# CanLogger_V22.net
KiCad netlist of a schematic drawn in EAGLE
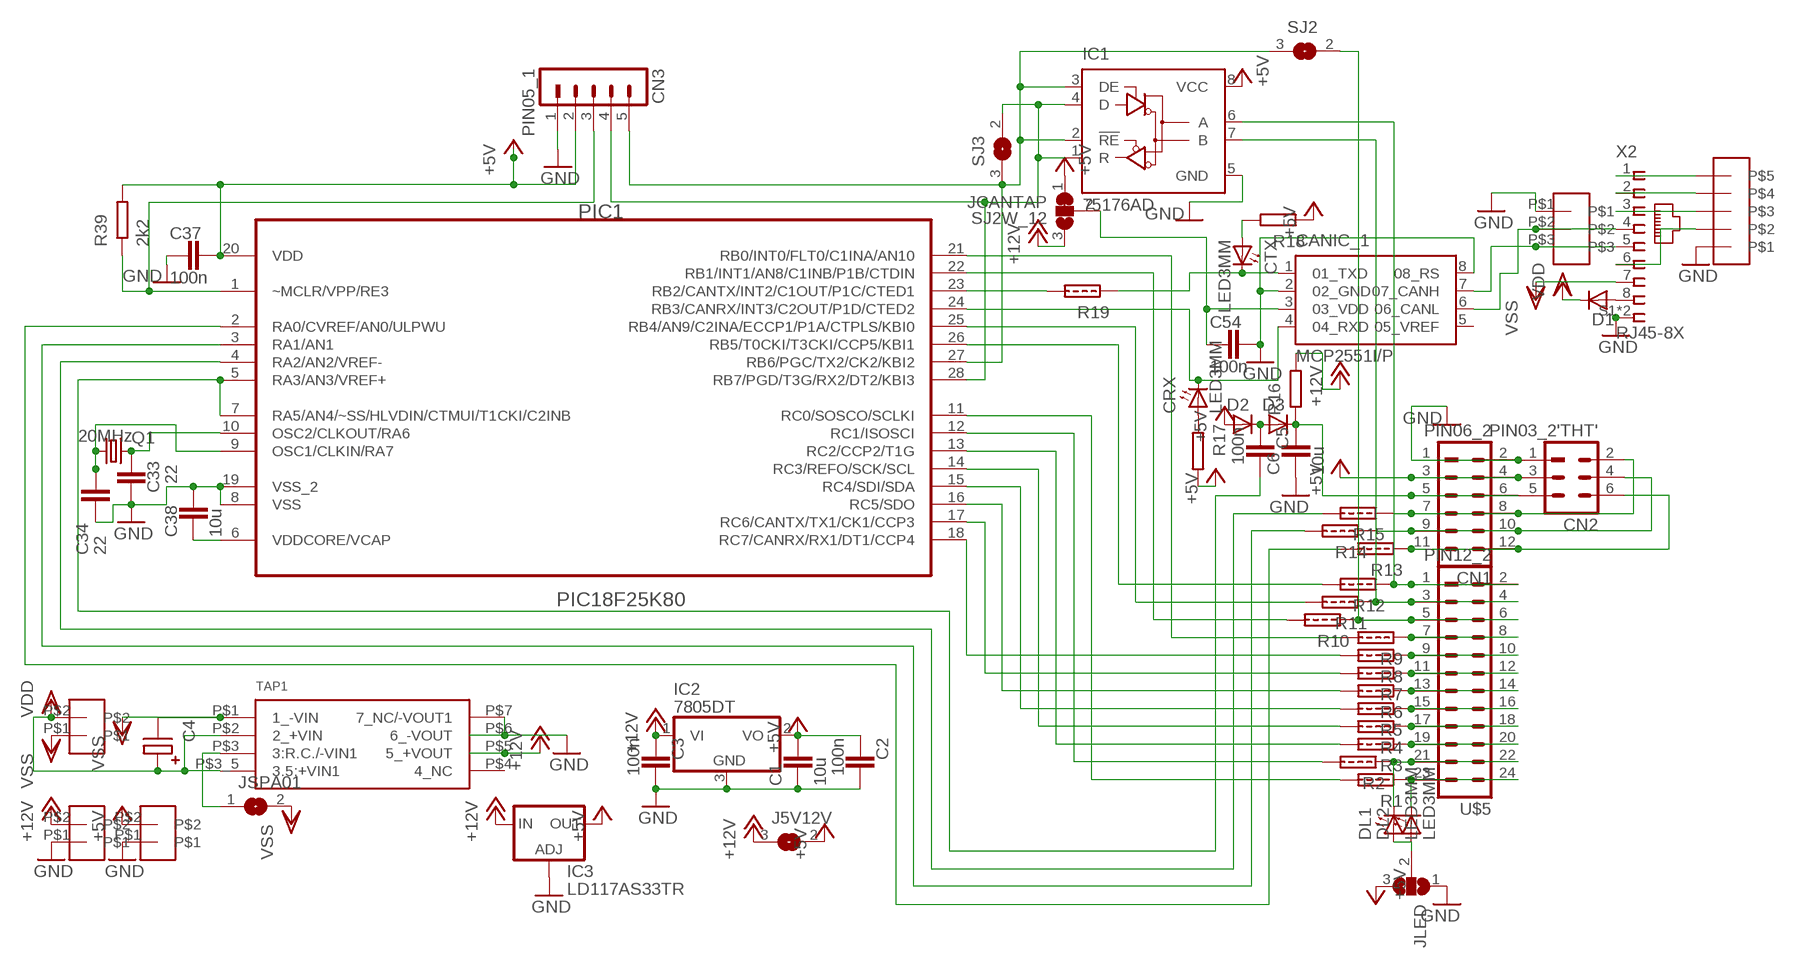
[diagram p0: schematic, sheet 1]

(export (version "E")
  (design (tool "Eeschema 10.0.6"))
  (components
    (comp (ref "C1")
      (value "10u")
      (footprint "eagle-import:R0805")
      (libsource (lib "eagle-import") (part "C0805"))
    )
    (comp (ref "C2")
      (value "100n")
      (footprint "eagle-import:R0805")
      (libsource (lib "eagle-import") (part "C0805"))
    )
    (comp (ref "C3")
      (value "100n")
      (footprint "eagle-import:R0805")
      (libsource (lib "eagle-import") (part "C0805"))
    )
    (comp (ref "C4")
      (value "C_EL1R05")
      (footprint "eagle-import:C_EL1RASZT05")
      (libsource (lib "eagle-import") (part "C_EL1R05"))
    )
    (comp (ref "C5")
      (value "100n")
      (footprint "eagle-import:R0805")
      (libsource (lib "eagle-import") (part "C0805"))
    )
    (comp (ref "C6")
      (value "10u")
      (footprint "eagle-import:R0805")
      (libsource (lib "eagle-import") (part "C0805"))
    )
    (comp (ref "C33")
      (value "22")
      (footprint "eagle-import:R0805")
      (libsource (lib "eagle-import") (part "C0805"))
    )
    (comp (ref "C34")
      (value "22")
      (footprint "eagle-import:R0805")
      (libsource (lib "eagle-import") (part "C0805"))
    )
    (comp (ref "C37")
      (value "100n")
      (footprint "eagle-import:R0805")
      (libsource (lib "eagle-import") (part "C0805"))
    )
    (comp (ref "C38")
      (value "10u")
      (footprint "eagle-import:R0805")
      (libsource (lib "eagle-import") (part "C0805"))
    )
    (comp (ref "C54")
      (value "100n")
      (footprint "eagle-import:R0805")
      (libsource (lib "eagle-import") (part "C0805"))
    )
    (comp (ref "CANIC_1")
      (value "MCP2551I/P")
      (footprint "eagle-import:DIL_8")
      (libsource (lib "eagle-import") (part "MCP2551I/P"))
    )
    (comp (ref "CN1")
      (value "PIN06_2")
      (footprint "eagle-import:PIN06_2")
      (libsource (lib "eagle-import") (part "PIN06_2"))
    )
    (comp (ref "CN2")
      (value "PIN03_2'THT'")
      (footprint "eagle-import:PIN03_2")
      (libsource (lib "eagle-import") (part "PIN03_2'THT'"))
    )
    (comp (ref "CN3")
      (value "PIN05_1")
      (footprint "eagle-import:PIN05_1")
      (libsource (lib "eagle-import") (part "PIN05_1"))
    )
    (comp (ref "CN_CAN")
      (value "FEHER_TUS_3")
      (footprint "eagle-import:FEHER_TUS_3")
      (libsource (lib "eagle-import") (part "FEHER_TUS_3"))
    )
    (comp (ref "CRX")
      (value "LED3MM")
      (footprint "eagle-import:LED3MM")
      (libsource (lib "eagle-import") (part "LED3MM"))
    )
    (comp (ref "CTX")
      (value "LED3MM")
      (footprint "eagle-import:LED3MM")
      (libsource (lib "eagle-import") (part "LED3MM"))
    )
    (comp (ref "D1")
      (value "D1RNAGY")
      (footprint "eagle-import:D1RASZTNAGY")
      (libsource (lib "eagle-import") (part "D1RNAGY"))
    )
    (comp (ref "D2")
      (value "D0805")
      (footprint "eagle-import:D0805")
      (libsource (lib "eagle-import") (part "D0805"))
    )
    (comp (ref "D3")
      (value "D0805")
      (footprint "eagle-import:D0805")
      (libsource (lib "eagle-import") (part "D0805"))
    )
    (comp (ref "DL1")
      (value "LED3MM")
      (footprint "eagle-import:LED3MM")
      (libsource (lib "eagle-import") (part "LED3MM"))
    )
    (comp (ref "DL2")
      (value "LED3MM")
      (footprint "eagle-import:LED3MM")
      (libsource (lib "eagle-import") (part "LED3MM"))
    )
    (comp (ref "IC1")
      (value "75176AD")
      (footprint "eagle-import:D_R-PDSO-G8")
      (libsource (lib "eagle-import") (part "75176AD"))
    )
    (comp (ref "IC2")
      (value "7805DT")
      (footprint "eagle-import:TO252")
      (libsource (lib "eagle-import") (part "78DT05"))
    )
    (comp (ref "IC3")
      (value "LD117AS33TR")
      (footprint "eagle-import:SOT223")
      (libsource (lib "eagle-import") (part "LD117A?S33TR"))
    )
    (comp (ref "J5V12V")
      (value "SJ")
      (footprint "eagle-import:SJ")
      (libsource (lib "eagle-import") (part "jumper2_SJ"))
    )
    (comp (ref "JCANTAP")
      (value "SJ2W_12")
      (footprint "eagle-import:SJ2_12")
      (libsource (lib "eagle-import") (part "SJ2W_12"))
    )
    (comp (ref "JLED")
      (value "SJ2W")
      (footprint "eagle-import:SJ2")
      (libsource (lib "eagle-import") (part "SJ2W"))
    )
    (comp (ref "JSPA01")
      (value "SJW")
      (footprint "eagle-import:SJW")
      (libsource (lib "eagle-import") (part "SJW"))
    )
    (comp (ref "PIC1")
      (value "PIC18F25K80")
      (footprint "eagle-import:SOIC127P1030X265-28N")
      (libsource (lib "eagle-import") (part "PIC18F25K80"))
    )
    (comp (ref "Q1")
      (value "20MHz")
      (footprint "eagle-import:XTAL_QS")
      (libsource (lib "eagle-import") (part "XTAL_2QS"))
    )
    (comp (ref "R1")
      (value "RNULL_EU0805")
      (footprint "eagle-import:R0805_C")
      (libsource (lib "eagle-import") (part "RNULL_EU0805"))
    )
    (comp (ref "R2")
      (value "RNULL_EU0805")
      (footprint "eagle-import:R0805_C")
      (libsource (lib "eagle-import") (part "RNULL_EU0805"))
    )
    (comp (ref "R3")
      (value "RNULL_EU0805")
      (footprint "eagle-import:R0805_C")
      (libsource (lib "eagle-import") (part "RNULL_EU0805"))
    )
    (comp (ref "R4")
      (value "RNULL_EU0805")
      (footprint "eagle-import:R0805_C")
      (libsource (lib "eagle-import") (part "RNULL_EU0805"))
    )
    (comp (ref "R5")
      (value "RNULL_EU0805")
      (footprint "eagle-import:R0805_C")
      (libsource (lib "eagle-import") (part "RNULL_EU0805"))
    )
    (comp (ref "R6")
      (value "RNULL_EU0805")
      (footprint "eagle-import:R0805_C")
      (libsource (lib "eagle-import") (part "RNULL_EU0805"))
    )
    (comp (ref "R7")
      (value "RNULL_EU0805")
      (footprint "eagle-import:R0805_C")
      (libsource (lib "eagle-import") (part "RNULL_EU0805"))
    )
    (comp (ref "R8")
      (value "RNULL_EU0805")
      (footprint "eagle-import:R0805_C")
      (libsource (lib "eagle-import") (part "RNULL_EU0805"))
    )
    (comp (ref "R9")
      (value "RNULL_EU0805")
      (footprint "eagle-import:R0805_C")
      (libsource (lib "eagle-import") (part "RNULL_EU0805"))
    )
    (comp (ref "R10")
      (value "RNULL_EU0805")
      (footprint "eagle-import:R0805_C")
      (libsource (lib "eagle-import") (part "RNULL_EU0805"))
    )
    (comp (ref "R11")
      (value "RNULL_EU0805")
      (footprint "eagle-import:R0805_C")
      (libsource (lib "eagle-import") (part "RNULL_EU0805"))
    )
    (comp (ref "R12")
      (value "RNULL_EU0805")
      (footprint "eagle-import:R0805_C")
      (libsource (lib "eagle-import") (part "RNULL_EU0805"))
    )
    (comp (ref "R13")
      (value "RNULL_EU0805")
      (footprint "eagle-import:R0805_C")
      (libsource (lib "eagle-import") (part "RNULL_EU0805"))
    )
    (comp (ref "R14")
      (value "RNULL_EU0805")
      (footprint "eagle-import:R0805_C")
      (libsource (lib "eagle-import") (part "RNULL_EU0805"))
    )
    (comp (ref "R15")
      (value "RNULL_EU0805")
      (footprint "eagle-import:R0805_C")
      (libsource (lib "eagle-import") (part "RNULL_EU0805"))
    )
    (comp (ref "R16")
      (value "R_EU0805")
      (footprint "eagle-import:R0805")
      (libsource (lib "eagle-import") (part "R_EU0805"))
    )
    (comp (ref "R17")
      (value "R_EU0805")
      (footprint "eagle-import:R0805")
      (libsource (lib "eagle-import") (part "R_EU0805"))
    )
    (comp (ref "R18")
      (value "R_EU0805")
      (footprint "eagle-import:R0805")
      (libsource (lib "eagle-import") (part "R_EU0805"))
    )
    (comp (ref "R19")
      (value "RNULL_EU0805")
      (footprint "eagle-import:R0805_C")
      (libsource (lib "eagle-import") (part "RNULL_EU0805"))
    )
    (comp (ref "R39")
      (value "2k2")
      (footprint "eagle-import:R0805")
      (libsource (lib "eagle-import") (part "R_EU0805"))
    )
    (comp (ref "SJ2")
      (value "SJ")
      (footprint "eagle-import:SJ")
      (libsource (lib "eagle-import") (part "jumper2_SJ"))
    )
    (comp (ref "SJ3")
      (value "SJ")
      (footprint "eagle-import:SJ")
      (libsource (lib "eagle-import") (part "jumper2_SJ"))
    )
    (comp (ref "TAP1")
      (value "SPA01_02C")
      (footprint "eagle-import:SPA01_02C")
      (libsource (lib "eagle-import") (part "SPA01_02C"))
    )
    (comp (ref "U$1")
      (value "FEHER_TUS_5")
      (footprint "eagle-import:FEHER_TUS_5")
      (libsource (lib "eagle-import") (part "FEHER_TUS_5"))
    )
    (comp (ref "U$2")
      (value "FEHER_TUS_2ALLO")
      (footprint "eagle-import:FEHER_TUS_2")
      (libsource (lib "eagle-import") (part "FEHER_TUS_2ALLO"))
    )
    (comp (ref "U$3")
      (value "FEHER_TUS_2ALLO")
      (footprint "eagle-import:FEHER_TUS_2")
      (libsource (lib "eagle-import") (part "FEHER_TUS_2ALLO"))
    )
    (comp (ref "U$4")
      (value "FEHER_TUS_2ALLO")
      (footprint "eagle-import:FEHER_TUS_2")
      (libsource (lib "eagle-import") (part "FEHER_TUS_2ALLO"))
    )
    (comp (ref "U$5")
      (value "PIN12_2")
      (footprint "eagle-import:PIN12_2")
      (libsource (lib "eagle-import") (part "PIN12_2"))
    )
    (comp (ref "X2")
      (value "RJ45-8X")
      (footprint "eagle-import:RJ45")
      (libsource (lib "eagle-import") (part "RJ45-8X"))
    )
  )
  (nets
    (net (code "1") (name "+5V") (class "Default")
      (node (ref "C1") (pin "1") (pinfunction "1_1") (pintype "passive"))
      (node (ref "C2") (pin "2") (pinfunction "2_2") (pintype "passive"))
      (node (ref "C37") (pin "1") (pinfunction "1_1") (pintype "passive"))
      (node (ref "CN1") (pin "3") (pinfunction "3_3") (pintype "passive"))
      (node (ref "CN1") (pin "4") (pinfunction "4_4") (pintype "passive"))
      (node (ref "CN2") (pin "3") (pinfunction "3_3") (pintype "passive"))
      (node (ref "CN3") (pin "2") (pinfunction "2_2") (pintype "passive"))
      (node (ref "D2") (pin "1") (pinfunction "A_1") (pintype "passive"))
      (node (ref "IC1") (pin "8") (pinfunction "VCC_8") (pintype "power_in"))
      (node (ref "IC2") (pin "2") (pinfunction "VO_2") (pintype "passive"))
      (node (ref "IC3") (pin "2") (pinfunction "OUT_2") (pintype "passive"))
      (node (ref "IC3") (pin "4") (pinfunction "OUT_4") (pintype "passive"))
      (node (ref "J5V12V") (pin "2") (pinfunction "2_2") (pintype "passive"))
      (node (ref "JCANTAP") (pin "1") (pinfunction "1_1") (pintype "passive"))
      (node (ref "JLED") (pin "3") (pinfunction "3_3") (pintype "passive"))
      (node (ref "PIC1") (pin "20") (pinfunction "VDD_20") (pintype "power_in"))
      (node (ref "R17") (pin "2") (pinfunction "E_2") (pintype "passive"))
      (node (ref "R18") (pin "1") (pinfunction "A_1") (pintype "passive"))
      (node (ref "R39") (pin "2") (pinfunction "E_2") (pintype "passive"))
      (node (ref "U$4") (pin "P$2") (pinfunction "P$2_P$2") (pintype "bidirectional"))
    )
    (net (code "2") (name "+12V") (class "Default")
      (node (ref "C3") (pin "2") (pinfunction "2_2") (pintype "passive"))
      (node (ref "IC2") (pin "1") (pinfunction "VI_1") (pintype "input"))
      (node (ref "IC3") (pin "3") (pinfunction "IN_3") (pintype "input"))
      (node (ref "J5V12V") (pin "3") (pinfunction "1_3") (pintype "passive"))
      (node (ref "JCANTAP") (pin "3") (pinfunction "3_3") (pintype "passive"))
      (node (ref "R16") (pin "2") (pinfunction "E_2") (pintype "passive"))
      (node (ref "TAP1") (pin "P$5") (pinfunction "5_+VOUT_P$5") (pintype "bidirectional"))
      (node (ref "U$3") (pin "P$2") (pinfunction "P$2_P$2") (pintype "bidirectional"))
    )
    (net (code "3") (name "GND") (class "Default")
      (node (ref "C1") (pin "2") (pinfunction "2_2") (pintype "passive"))
      (node (ref "C2") (pin "1") (pinfunction "1_1") (pintype "passive"))
      (node (ref "C3") (pin "1") (pinfunction "1_1") (pintype "passive"))
      (node (ref "C33") (pin "2") (pinfunction "2_2") (pintype "passive"))
      (node (ref "C34") (pin "2") (pinfunction "2_2") (pintype "passive"))
      (node (ref "C37") (pin "2") (pinfunction "2_2") (pintype "passive"))
      (node (ref "C38") (pin "1") (pinfunction "1_1") (pintype "passive"))
      (node (ref "C54") (pin "1") (pinfunction "1_1") (pintype "passive"))
      (node (ref "C6") (pin "2") (pinfunction "2_2") (pintype "passive"))
      (node (ref "CANIC_1") (pin "2") (pinfunction "02_GND_2") (pintype "power_in"))
      (node (ref "CANIC_1") (pin "8") (pinfunction "08_RS_8") (pintype "input"))
      (node (ref "CN1") (pin "1") (pinfunction "1_1") (pintype "passive"))
      (node (ref "CN1") (pin "2") (pinfunction "2_2") (pintype "passive"))
      (node (ref "CN2") (pin "1") (pinfunction "1_1") (pintype "passive"))
      (node (ref "CN3") (pin "1") (pinfunction "1_1") (pintype "passive"))
      (node (ref "CN_CAN") (pin "P$1") (pinfunction "P$1_P$1") (pintype "bidirectional"))
      (node (ref "IC1") (pin "5") (pinfunction "GND_5") (pintype "power_in"))
      (node (ref "IC2") (pin "3") (pinfunction "GND_3") (pintype "passive"))
      (node (ref "IC3") (pin "1") (pinfunction "ADJ_1") (pintype "input"))
      (node (ref "JLED") (pin "1") (pinfunction "1_1") (pintype "passive"))
      (node (ref "PIC1") (pin "19") (pinfunction "VSS_2_19") (pintype "power_in"))
      (node (ref "PIC1") (pin "8") (pinfunction "VSS_8") (pintype "power_in"))
      (node (ref "TAP1") (pin "P$6") (pinfunction "6_-VOUT_P$6") (pintype "bidirectional"))
      (node (ref "TAP1") (pin "P$7") (pinfunction "7_NC/-VOUT1_P$7") (pintype "bidirectional"))
      (node (ref "U$1") (pin "P$1") (pinfunction "P$1_P$1") (pintype "bidirectional"))
      (node (ref "U$3") (pin "P$1") (pinfunction "P$1_P$1") (pintype "bidirectional"))
      (node (ref "U$4") (pin "P$1") (pinfunction "P$1_P$1") (pintype "bidirectional"))
      (node (ref "X2") (pin "S1") (pinfunction "S_S1") (pintype "passive"))
      (node (ref "X2") (pin "S2") (pinfunction "S_S2") (pintype "passive"))
    )
    (net (code "4") (name "Net-(CANIC_1-01_TXD)") (class "Default")
      (node (ref "CANIC_1") (pin "1") (pinfunction "01_TXD_1") (pintype "input"))
      (node (ref "CTX") (pin "K") (pinfunction "C_K") (pintype "passive"))
      (node (ref "R19") (pin "1") (pinfunction "A_1") (pintype "passive"))
    )
    (net (code "5") (name "Net-(CANIC_1-03_VDD)") (class "Default")
      (node (ref "C54") (pin "2") (pinfunction "2_2") (pintype "passive"))
      (node (ref "CANIC_1") (pin "3") (pinfunction "03_VDD_3") (pintype "power_in"))
      (node (ref "JCANTAP") (pin "2") (pinfunction "2_2") (pintype "passive"))
    )
    (net (code "6") (name "Net-(CANIC_1-04_RXD)") (class "Default")
      (node (ref "CANIC_1") (pin "4") (pinfunction "04_RXD_4") (pintype "output"))
      (node (ref "CRX") (pin "K") (pinfunction "C_K") (pintype "passive"))
      (node (ref "PIC1") (pin "24") (pinfunction "RB3/CANRX/INT3/C2OUT/P1D/CTED2_24") (pintype "bidirectional"))
    )
    (net (code "7") (name "Net-(CANIC_1-06_CANL)") (class "Default")
      (node (ref "CANIC_1") (pin "6") (pinfunction "06_CANL_6") (pintype "bidirectional"))
      (node (ref "CN_CAN") (pin "P$2") (pinfunction "P$2_P$2") (pintype "bidirectional"))
      (node (ref "X2") (pin "4") (pinfunction "4_4") (pintype "passive"))
    )
    (net (code "8") (name "Net-(CANIC_1-07_CANH)") (class "Default")
      (node (ref "CANIC_1") (pin "7") (pinfunction "07_CANH_7") (pintype "bidirectional"))
      (node (ref "CN_CAN") (pin "P$3") (pinfunction "P$3_P$3") (pintype "bidirectional"))
      (node (ref "X2") (pin "5") (pinfunction "5_5") (pintype "passive"))
    )
    (net (code "9") (name "Net-(D1-A)") (class "Default")
      (node (ref "D1") (pin "P$1") (pinfunction "A_P$1") (pintype "passive"))
      (node (ref "X2") (pin "8") (pinfunction "8_8") (pintype "passive"))
    )
    (net (code "10") (name "Net-(D2-C)") (class "Default")
      (node (ref "C5") (pin "2") (pinfunction "2_2") (pintype "passive"))
      (node (ref "D2") (pin "2") (pinfunction "C_2") (pintype "passive"))
      (node (ref "D3") (pin "1") (pinfunction "A_1") (pintype "passive"))
    )
    (net (code "11") (name "Net-(D3-C)") (class "Default")
      (node (ref "C6") (pin "1") (pinfunction "1_1") (pintype "passive"))
      (node (ref "CN1") (pin "5") (pinfunction "5_5") (pintype "passive"))
      (node (ref "CN1") (pin "6") (pinfunction "6_6") (pintype "passive"))
      (node (ref "CN2") (pin "5") (pinfunction "5_5") (pintype "passive"))
      (node (ref "D3") (pin "2") (pinfunction "C_2") (pintype "passive"))
      (node (ref "R16") (pin "1") (pinfunction "A_1") (pintype "passive"))
    )
    (net (code "12") (name "Net-(DL1-C)") (class "Default")
      (node (ref "DL1") (pin "K") (pinfunction "C_K") (pintype "passive"))
      (node (ref "R2") (pin "1") (pinfunction "A_1") (pintype "passive"))
      (node (ref "U$5") (pin "21") (pinfunction "21_21") (pintype "passive"))
      (node (ref "U$5") (pin "22") (pinfunction "22_22") (pintype "passive"))
    )
    (net (code "13") (name "Net-(DL1-PadA)") (class "Default")
      (node (ref "DL1") (pin "A") (pinfunction "A_A") (pintype "passive"))
      (node (ref "DL2") (pin "A") (pinfunction "A_A") (pintype "passive"))
      (node (ref "JLED") (pin "2") (pinfunction "2_2") (pintype "passive"))
    )
    (net (code "14") (name "Net-(DL2-C)") (class "Default")
      (node (ref "DL2") (pin "K") (pinfunction "C_K") (pintype "passive"))
      (node (ref "R1") (pin "1") (pinfunction "A_1") (pintype "passive"))
      (node (ref "U$5") (pin "23") (pinfunction "23_23") (pintype "passive"))
      (node (ref "U$5") (pin "24") (pinfunction "24_24") (pintype "passive"))
    )
    (net (code "15") (name "Net-(IC1-A)") (class "Default")
      (node (ref "IC1") (pin "6") (pinfunction "A_6") (pintype "output"))
      (node (ref "R12") (pin "1") (pinfunction "A_1") (pintype "passive"))
      (node (ref "U$5") (pin "1") (pinfunction "1_1") (pintype "passive"))
      (node (ref "U$5") (pin "2") (pinfunction "2_2") (pintype "passive"))
    )
    (net (code "16") (name "Net-(IC1-B)") (class "Default")
      (node (ref "IC1") (pin "7") (pinfunction "B_7") (pintype "output"))
      (node (ref "R11") (pin "1") (pinfunction "A_1") (pintype "passive"))
      (node (ref "U$5") (pin "3") (pinfunction "3_3") (pintype "passive"))
      (node (ref "U$5") (pin "4") (pinfunction "4_4") (pintype "passive"))
    )
    (net (code "17") (name "Net-(IC1-D)") (class "Default")
      (node (ref "CN3") (pin "4") (pinfunction "4_4") (pintype "passive"))
      (node (ref "IC1") (pin "1") (pinfunction "R_1") (pintype "input"))
      (node (ref "IC1") (pin "4") (pinfunction "D_4") (pintype "input"))
      (node (ref "PIC1") (pin "28") (pinfunction "RB7/PGD/T3G/RX2/DT2/KBI3_28") (pintype "bidirectional"))
      (node (ref "SJ3") (pin "2") (pinfunction "2_2") (pintype "passive"))
    )
    (net (code "18") (name "Net-(IC1-DE)") (class "Default")
      (node (ref "CN3") (pin "5") (pinfunction "5_5") (pintype "passive"))
      (node (ref "IC1") (pin "2") (pinfunction "~{RE}_2") (pintype "input"))
      (node (ref "IC1") (pin "3") (pinfunction "DE_3") (pintype "input"))
      (node (ref "PIC1") (pin "27") (pinfunction "RB6/PGC/TX2/CK2/KBI2_27") (pintype "bidirectional"))
      (node (ref "SJ2") (pin "3") (pinfunction "1_3") (pintype "passive"))
      (node (ref "SJ3") (pin "3") (pinfunction "1_3") (pintype "passive"))
    )
    (net (code "19") (name "Net-(PIC1-OSC1{slash}CLKIN{slash}RA7)") (class "Default")
      (node (ref "C34") (pin "1") (pinfunction "1_1") (pintype "passive"))
      (node (ref "PIC1") (pin "9") (pinfunction "OSC1/CLKIN/RA7_9") (pintype "bidirectional"))
      (node (ref "Q1") (pin "1") (pinfunction "1_1") (pintype "passive"))
    )
    (net (code "20") (name "Net-(PIC1-OSC2{slash}CLKOUT{slash}RA6)") (class "Default")
      (node (ref "C33") (pin "1") (pinfunction "1_1") (pintype "passive"))
      (node (ref "PIC1") (pin "10") (pinfunction "OSC2/CLKOUT/RA6_10") (pintype "bidirectional"))
      (node (ref "Q1") (pin "2") (pinfunction "2_2") (pintype "passive"))
    )
    (net (code "21") (name "Net-(PIC1-RA0{slash}CVREF{slash}AN0{slash}ULPWU)") (class "Default")
      (node (ref "PIC1") (pin "2") (pinfunction "RA0/CVREF/AN0/ULPWU_2") (pintype "bidirectional"))
      (node (ref "R13") (pin "2") (pinfunction "E_2") (pintype "passive"))
    )
    (net (code "22") (name "Net-(PIC1-RA1{slash}AN1)") (class "Default")
      (node (ref "PIC1") (pin "3") (pinfunction "RA1/AN1_3") (pintype "bidirectional"))
      (node (ref "R14") (pin "2") (pinfunction "E_2") (pintype "passive"))
    )
    (net (code "23") (name "Net-(PIC1-RA2{slash}AN2{slash}VREF-)") (class "Default")
      (node (ref "PIC1") (pin "4") (pinfunction "RA2/AN2/VREF-_4") (pintype "bidirectional"))
      (node (ref "R15") (pin "2") (pinfunction "E_2") (pintype "passive"))
    )
    (net (code "24") (name "Net-(PIC1-RA3{slash}AN3{slash}VREF+)") (class "Default")
      (node (ref "C5") (pin "1") (pinfunction "1_1") (pintype "passive"))
      (node (ref "PIC1") (pin "5") (pinfunction "RA3/AN3/VREF+_5") (pintype "bidirectional"))
      (node (ref "PIC1") (pin "7") (pinfunction "RA5/AN4/~{SS/HLVDIN/CTMUI/T1CKI/C2INB}_7") (pintype "bidirectional"))
    )
    (net (code "25") (name "Net-(PIC1-RB0{slash}INT0{slash}FLT0{slash}C1INA{slash}AN10)") (class "Default")
      (node (ref "PIC1") (pin "21") (pinfunction "RB0/INT0/FLT0/C1INA/AN10_21") (pintype "bidirectional"))
      (node (ref "R9") (pin "2") (pinfunction "E_2") (pintype "passive"))
    )
    (net (code "26") (name "Net-(PIC1-RB1{slash}INT1{slash}AN8{slash}C1INB{slash}P1B{slash}CTDIN)") (class "Default")
      (node (ref "PIC1") (pin "22") (pinfunction "RB1/INT1/AN8/C1INB/P1B/CTDIN_22") (pintype "bidirectional"))
      (node (ref "R10") (pin "2") (pinfunction "E_2") (pintype "passive"))
    )
    (net (code "27") (name "Net-(PIC1-RB2{slash}CANTX{slash}INT2{slash}C1OUT{slash}P1C{slash}CTED1)") (class "Default")
      (node (ref "PIC1") (pin "23") (pinfunction "RB2/CANTX/INT2/C1OUT/P1C/CTED1_23") (pintype "bidirectional"))
      (node (ref "R19") (pin "2") (pinfunction "E_2") (pintype "passive"))
    )
    (net (code "28") (name "Net-(PIC1-RB4{slash}AN9{slash}C2INA{slash}ECCP1{slash}P1A{slash}CTPLS{slash}KBI0)") (class "Default")
      (node (ref "PIC1") (pin "25") (pinfunction "RB4/AN9/C2INA/ECCP1/P1A/CTPLS/KBI0_25") (pintype "bidirectional"))
      (node (ref "R11") (pin "2") (pinfunction "E_2") (pintype "passive"))
    )
    (net (code "29") (name "Net-(PIC1-RB5{slash}T0CKI{slash}T3CKI{slash}CCP5{slash}KBI1)") (class "Default")
      (node (ref "PIC1") (pin "26") (pinfunction "RB5/T0CKI/T3CKI/CCP5/KBI1_26") (pintype "bidirectional"))
      (node (ref "R12") (pin "2") (pinfunction "E_2") (pintype "passive"))
    )
    (net (code "30") (name "Net-(PIC1-RC0{slash}SOSCO{slash}SCLKI)") (class "Default")
      (node (ref "PIC1") (pin "11") (pinfunction "RC0/SOSCO/SCLKI_11") (pintype "bidirectional"))
      (node (ref "R1") (pin "2") (pinfunction "E_2") (pintype "passive"))
    )
    (net (code "31") (name "Net-(PIC1-RC1{slash}ISOSCI)") (class "Default")
      (node (ref "PIC1") (pin "12") (pinfunction "RC1/ISOSCI_12") (pintype "bidirectional"))
      (node (ref "R2") (pin "2") (pinfunction "E_2") (pintype "passive"))
    )
    (net (code "32") (name "Net-(PIC1-RC2{slash}CCP2{slash}T1G)") (class "Default")
      (node (ref "PIC1") (pin "13") (pinfunction "RC2/CCP2/T1G_13") (pintype "bidirectional"))
      (node (ref "R3") (pin "2") (pinfunction "E_2") (pintype "passive"))
    )
    (net (code "33") (name "Net-(PIC1-RC3{slash}REFO{slash}SCK{slash}SCL)") (class "Default")
      (node (ref "PIC1") (pin "14") (pinfunction "RC3/REFO/SCK/SCL_14") (pintype "bidirectional"))
      (node (ref "R4") (pin "2") (pinfunction "E_2") (pintype "passive"))
    )
    (net (code "34") (name "Net-(PIC1-RC4{slash}SDI{slash}SDA)") (class "Default")
      (node (ref "PIC1") (pin "15") (pinfunction "RC4/SDI/SDA_15") (pintype "bidirectional"))
      (node (ref "R5") (pin "2") (pinfunction "E_2") (pintype "passive"))
    )
    (net (code "35") (name "Net-(PIC1-RC5{slash}SDO)") (class "Default")
      (node (ref "PIC1") (pin "16") (pinfunction "RC5/SDO_16") (pintype "bidirectional"))
      (node (ref "R6") (pin "2") (pinfunction "E_2") (pintype "passive"))
    )
    (net (code "36") (name "Net-(PIC1-RC6{slash}CANTX{slash}TX1{slash}CK1{slash}CCP3)") (class "Default")
      (node (ref "PIC1") (pin "17") (pinfunction "RC6/CANTX/TX1/CK1/CCP3_17") (pintype "bidirectional"))
      (node (ref "R7") (pin "2") (pinfunction "E_2") (pintype "passive"))
    )
    (net (code "37") (name "Net-(PIC1-RC7{slash}CANRX{slash}RX1{slash}DT1{slash}CCP4)") (class "Default")
      (node (ref "PIC1") (pin "18") (pinfunction "RC7/CANRX/RX1/DT1/CCP4_18") (pintype "bidirectional"))
      (node (ref "R8") (pin "2") (pinfunction "E_2") (pintype "passive"))
    )
    (net (code "38") (name "Net-(PIC1-VDDCORE{slash}VCAP)") (class "Default")
      (node (ref "C38") (pin "2") (pinfunction "2_2") (pintype "passive"))
      (node (ref "PIC1") (pin "6") (pinfunction "VDDCORE/VCAP_6") (pintype "bidirectional"))
    )
    (net (code "39") (name "Net-(PIC1-~{MCLR{slash}VPP{slash}RE3})") (class "Default")
      (node (ref "CN3") (pin "3") (pinfunction "3_3") (pintype "passive"))
      (node (ref "PIC1") (pin "1") (pinfunction "~{MCLR/VPP/RE3}_1") (pintype "input"))
      (node (ref "R39") (pin "1") (pinfunction "A_1") (pintype "passive"))
    )
    (net (code "40") (name "Net-(R3-A)") (class "Default")
      (node (ref "R3") (pin "1") (pinfunction "A_1") (pintype "passive"))
      (node (ref "U$5") (pin "19") (pinfunction "19_19") (pintype "passive"))
      (node (ref "U$5") (pin "20") (pinfunction "20_20") (pintype "passive"))
    )
    (net (code "41") (name "Net-(R4-A)") (class "Default")
      (node (ref "R4") (pin "1") (pinfunction "A_1") (pintype "passive"))
      (node (ref "U$5") (pin "17") (pinfunction "17_17") (pintype "passive"))
      (node (ref "U$5") (pin "18") (pinfunction "18_18") (pintype "passive"))
    )
    (net (code "42") (name "Net-(R5-A)") (class "Default")
      (node (ref "R5") (pin "1") (pinfunction "A_1") (pintype "passive"))
      (node (ref "U$5") (pin "15") (pinfunction "15_15") (pintype "passive"))
      (node (ref "U$5") (pin "16") (pinfunction "16_16") (pintype "passive"))
    )
    (net (code "43") (name "Net-(R6-A)") (class "Default")
      (node (ref "R6") (pin "1") (pinfunction "A_1") (pintype "passive"))
      (node (ref "U$5") (pin "13") (pinfunction "13_13") (pintype "passive"))
      (node (ref "U$5") (pin "14") (pinfunction "14_14") (pintype "passive"))
    )
    (net (code "44") (name "Net-(R7-A)") (class "Default")
      (node (ref "R7") (pin "1") (pinfunction "A_1") (pintype "passive"))
      (node (ref "U$5") (pin "11") (pinfunction "11_11") (pintype "passive"))
      (node (ref "U$5") (pin "12") (pinfunction "12_12") (pintype "passive"))
    )
    (net (code "45") (name "Net-(R8-A)") (class "Default")
      (node (ref "R8") (pin "1") (pinfunction "A_1") (pintype "passive"))
      (node (ref "U$5") (pin "10") (pinfunction "10_10") (pintype "passive"))
      (node (ref "U$5") (pin "9") (pinfunction "9_9") (pintype "passive"))
    )
    (net (code "46") (name "Net-(R9-A)") (class "Default")
      (node (ref "R9") (pin "1") (pinfunction "A_1") (pintype "passive"))
      (node (ref "U$5") (pin "7") (pinfunction "7_7") (pintype "passive"))
      (node (ref "U$5") (pin "8") (pinfunction "8_8") (pintype "passive"))
    )
    (net (code "47") (name "Net-(R10-A)") (class "Default")
      (node (ref "R10") (pin "1") (pinfunction "A_1") (pintype "passive"))
      (node (ref "SJ2") (pin "2") (pinfunction "2_2") (pintype "passive"))
      (node (ref "U$5") (pin "5") (pinfunction "5_5") (pintype "passive"))
      (node (ref "U$5") (pin "6") (pinfunction "6_6") (pintype "passive"))
    )
    (net (code "48") (name "Net-(R13-A)") (class "Default")
      (node (ref "CN1") (pin "11") (pinfunction "11_11") (pintype "passive"))
      (node (ref "CN1") (pin "12") (pinfunction "12_12") (pintype "passive"))
      (node (ref "CN2") (pin "6") (pinfunction "6_6") (pintype "passive"))
      (node (ref "R13") (pin "1") (pinfunction "A_1") (pintype "passive"))
    )
    (net (code "49") (name "Net-(R14-A)") (class "Default")
      (node (ref "CN1") (pin "10") (pinfunction "10_10") (pintype "passive"))
      (node (ref "CN1") (pin "9") (pinfunction "9_9") (pintype "passive"))
      (node (ref "CN2") (pin "4") (pinfunction "4_4") (pintype "passive"))
      (node (ref "R14") (pin "1") (pinfunction "A_1") (pintype "passive"))
    )
    (net (code "50") (name "Net-(R15-A)") (class "Default")
      (node (ref "CN1") (pin "7") (pinfunction "7_7") (pintype "passive"))
      (node (ref "CN1") (pin "8") (pinfunction "8_8") (pintype "passive"))
      (node (ref "CN2") (pin "2") (pinfunction "2_2") (pintype "passive"))
      (node (ref "R15") (pin "1") (pinfunction "A_1") (pintype "passive"))
    )
    (net (code "51") (name "Net-(R17-A)") (class "Default")
      (node (ref "CRX") (pin "A") (pinfunction "A_A") (pintype "passive"))
      (node (ref "R17") (pin "1") (pinfunction "A_1") (pintype "passive"))
    )
    (net (code "52") (name "Net-(R18-E)") (class "Default")
      (node (ref "CTX") (pin "A") (pinfunction "A_A") (pintype "passive"))
      (node (ref "R18") (pin "2") (pinfunction "E_2") (pintype "passive"))
    )
    (net (code "53") (name "Net-(TAP1-3:R.C.{slash}-VIN1)") (class "Default")
      (node (ref "JSPA01") (pin "1") (pinfunction "1_1") (pintype "passive"))
      (node (ref "TAP1") (pin "P$3") (pinfunction "3:R.C./-VIN1_P$3") (pintype "bidirectional"))
    )
    (net (code "54") (name "Net-(U$1-PadP$2)") (class "Default")
      (node (ref "U$1") (pin "P$2") (pinfunction "P$2_P$2") (pintype "bidirectional"))
      (node (ref "X2") (pin "6") (pinfunction "6_6") (pintype "passive"))
    )
    (net (code "55") (name "Net-(U$1-PadP$3)") (class "Default")
      (node (ref "U$1") (pin "P$3") (pinfunction "P$3_P$3") (pintype "bidirectional"))
      (node (ref "X2") (pin "3") (pinfunction "3_3") (pintype "passive"))
    )
    (net (code "56") (name "Net-(U$1-PadP$4)") (class "Default")
      (node (ref "U$1") (pin "P$4") (pinfunction "P$4_P$4") (pintype "bidirectional"))
      (node (ref "X2") (pin "2") (pinfunction "2_2") (pintype "passive"))
    )
    (net (code "57") (name "Net-(U$1-PadP$5)") (class "Default")
      (node (ref "U$1") (pin "P$5") (pinfunction "P$5_P$5") (pintype "bidirectional"))
      (node (ref "X2") (pin "1") (pinfunction "1_1") (pintype "passive"))
    )
    (net (code "58") (name "VDD") (class "Default")
      (node (ref "C4") (pin "P+") (pinfunction "P+_P+") (pintype "passive"))
      (node (ref "D1") (pin "P$2") (pinfunction "C_P$2") (pintype "passive"))
      (node (ref "TAP1") (pin "P$2") (pinfunction "2_+VIN_P$2") (pintype "bidirectional"))
      (node (ref "TAP1") (pin "P$3_5") (pinfunction "3.5:+VIN1_P$3_5") (pintype "bidirectional"))
      (node (ref "U$2") (pin "P$2") (pinfunction "P$2_P$2") (pintype "bidirectional"))
    )
    (net (code "59") (name "VSS") (class "Default")
      (node (ref "C4") (pin "P-") (pinfunction "P-_P-") (pintype "passive"))
      (node (ref "JSPA01") (pin "2") (pinfunction "2_2") (pintype "passive"))
      (node (ref "TAP1") (pin "P$1") (pinfunction "1_-VIN_P$1") (pintype "bidirectional"))
      (node (ref "U$2") (pin "P$1") (pinfunction "P$1_P$1") (pintype "bidirectional"))
      (node (ref "X2") (pin "7") (pinfunction "7_7") (pintype "passive"))
    )
    (net (code "60") (name "unconnected-(CANIC_1-05_VREF-Pad5)") (class "Default")
      (node (ref "CANIC_1") (pin "5") (pinfunction "05_VREF_5") (pintype "input"))
    )
    (net (code "61") (name "unconnected-(TAP1-4_NC-PadP$4)") (class "Default")
      (node (ref "TAP1") (pin "P$4") (pinfunction "4_NC_P$4") (pintype "bidirectional"))
    )
  )
)
